# Soldeerbout_P3.net
KiCad netlist of a schematic drawn in Altium Designer
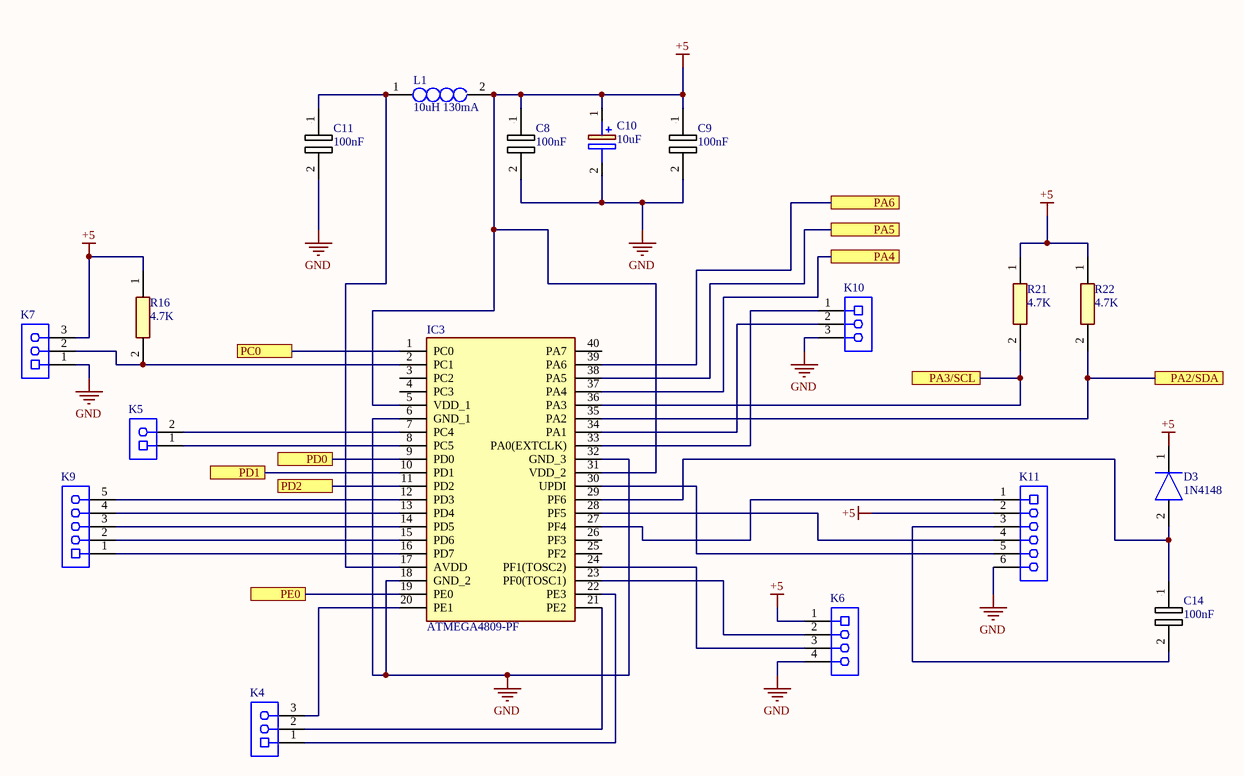
[diagram p0: Soldeerbout_P3.SchDoc]

(export (version "E")
  (design (tool "Eeschema 10.0.6"))
  (components
    (comp (ref "C8")
      (value "100nF")
      (footprint "SamacSys:0805")
      (description "Resistor")
      (fields (field (name "MANUFACTURER_PART_NUMBER") "ESR10EZPJ183"))
      (libsource (lib "SamacSys") (part "ESR10EZPJ183_1"))
    )
    (comp (ref "C9")
      (value "100nF")
      (footprint "SamacSys:0805")
      (description "Resistor")
      (fields (field (name "MANUFACTURER_PART_NUMBER") "ESR10EZPJ183"))
      (libsource (lib "SamacSys") (part "ESR10EZPJ183_1"))
    )
    (comp (ref "C10")
      (value "10uF")
      (footprint "SamacSys:C 50V 10µF")
      (description "Capacitor Polarised")
      (fields (field (name "MANUFACTURER_PART_NUMBER") "ESS106M050AE2AA"))
      (libsource (lib "SamacSys") (part "ESS106M050AE2AA"))
    )
    (comp (ref "C11")
      (value "100nF")
      (footprint "SamacSys:0805")
      (description "Resistor")
      (fields (field (name "MANUFACTURER_PART_NUMBER") "ESR10EZPJ183"))
      (libsource (lib "SamacSys") (part "ESR10EZPJ183_1"))
    )
    (comp (ref "C14")
      (value "100nF")
      (footprint "SamacSys:0805")
      (description "Resistor")
      (fields (field (name "MANUFACTURER_PART_NUMBER") "ESR10EZPJ183"))
      (libsource (lib "SamacSys") (part "ESR10EZPJ183_1"))
    )
    (comp (ref "D3")
      (value "1N4148")
      (footprint "SamacSys:1N4148, 100V 200mA")
      (description "Diode")
      (libsource (lib "SamacSys") (part "1N4148"))
    )
    (comp (ref "IC3")
      (value "ATMEGA4809-PF")
      (footprint "SamacSys:ic3")
      (description "Integrated Circuit")
      (fields (field (name "MOUSER2 PART NUMBER") "556-ATMEGA4809-PF"))
      (libsource (lib "SamacSys") (part "ATMEGA4809-PF"))
    )
    (comp (ref "K4")
      (value "61300311821")
      (footprint "61300311821")
      (description "WR-PHD Socket Header, THT, pitch 2.54mm, Single Row, Vertical, 3p")
      (fields (field (name "MANUFACTURER") "Wurth Elektronik"))
      (libsource (lib "") (part "61300311821_1"))
    )
    (comp (ref "K5")
      (value "61300211821")
      (footprint "61300211821")
      (description "WR-PHD Socket Header, THT, pitch 2.54mm, Single Row, Vertical, 2p")
      (fields (field (name "MANUFACTURER") "Wurth Elektronik"))
      (libsource (lib "SamacSys") (part "61300211821"))
    )
    (comp (ref "K6")
      (value "61300411821")
      (footprint "61300411821")
      (description "WR-PHD Socket Header, THT, pitch 2.54mm, Single Row, Vertical, 4p")
      (fields (field (name "MANUFACTURER") "Wurth Elektronik"))
      (libsource (lib "SamacSys") (part "61300411821"))
    )
    (comp (ref "K7")
      (value "61300311821")
      (footprint "61300311821")
      (description "WR-PHD Socket Header, THT, pitch 2.54mm, Single Row, Vertical, 3p")
      (fields (field (name "MANUFACTURER") "Wurth Elektronik"))
      (libsource (lib "") (part "61300311821_1"))
    )
    (comp (ref "K9")
      (value "61300511821")
      (footprint "61300511821")
      (description "WR-PHD Socket Header, THT, pitch 2.54mm, Single Row, Vertical, 5p")
      (fields (field (name "MANUFACTURER") "Wurth Elektronik"))
      (libsource (lib "SamacSys") (part "61300511821"))
    )
    (comp (ref "K10")
      (value "61300311821")
      (footprint "61300311821")
      (description "WR-PHD Socket Header, THT, pitch 2.54mm, Single Row, Vertical, 3p")
      (fields (field (name "MANUFACTURER") "Wurth Elektronik"))
      (libsource (lib "SamacSys") (part "61300311821"))
    )
    (comp (ref "K11")
      (value "61300611821")
      (footprint "61300611821")
      (description "WR-PHD Socket Header, THT, pitch 2.54mm, Single Row, Vertical, 6p")
      (fields (field (name "MANUFACTURER") "Wurth Elektronik"))
      (libsource (lib "SamacSys") (part "61300611821"))
    )
    (comp (ref "L1")
      (value "10uH 130mA")
      (footprint "SamacSys:L1 10uH 130mA")
      (description "Inductor")
      (fields
        (field (name "MOUSER2 PART NUMBER") "542-78F100-RC")
        (field (name "MANUFACTURER_PART_NUMBER") "78F100J-RC")
      )
      (libsource (lib "SamacSys") (part "78F100J-RC"))
    )
    (comp (ref "R16")
      (value "4.7K")
      (footprint "SamacSys:0805")
      (description "Resistor")
      (fields (field (name "MANUFACTURER_PART_NUMBER") "ESR10EZPJ183"))
      (libsource (lib "SamacSys") (part "ESR10EZPJ183"))
    )
    (comp (ref "R21")
      (value "4.7K")
      (footprint "SamacSys:0805")
      (description "Resistor")
      (fields (field (name "MANUFACTURER_PART_NUMBER") "ESR10EZPJ183"))
      (libsource (lib "SamacSys") (part "ESR10EZPJ183"))
    )
    (comp (ref "R22")
      (value "4.7K")
      (footprint "SamacSys:0805")
      (description "Resistor")
      (fields (field (name "MANUFACTURER_PART_NUMBER") "ESR10EZPJ183"))
      (libsource (lib "SamacSys") (part "ESR10EZPJ183"))
    )
  )
  (nets
    (net (code "1") (name "+5") (class "Default")
      (node (ref "C10") (pin "1") (pinfunction "+_1") (pintype "passive"))
      (node (ref "C8") (pin "1") (pinfunction "1_1") (pintype "passive"))
      (node (ref "C9") (pin "1") (pinfunction "1_1") (pintype "passive"))
      (node (ref "D3") (pin "1") (pinfunction "K_1") (pintype "passive"))
      (node (ref "IC3") (pin "31") (pinfunction "VDD_2_31") (pintype "passive"))
      (node (ref "IC3") (pin "5") (pinfunction "VDD_1_5") (pintype "passive"))
      (node (ref "K11") (pin "2") (pinfunction "2_2") (pintype "passive"))
      (node (ref "K6") (pin "1") (pinfunction "1_1") (pintype "passive"))
      (node (ref "K7") (pin "3") (pinfunction "3_3") (pintype "passive"))
      (node (ref "L1") (pin "2") (pinfunction "2_2") (pintype "passive"))
      (node (ref "R16") (pin "1") (pinfunction "1_1") (pintype "passive"))
      (node (ref "R21") (pin "1") (pinfunction "1_1") (pintype "passive"))
      (node (ref "R22") (pin "1") (pinfunction "1_1") (pintype "passive"))
    )
    (net (code "2") (name "/PA2{slash}SDA") (class "Default")
      (node (ref "IC3") (pin "35") (pinfunction "PA2_35") (pintype "passive"))
      (node (ref "R22") (pin "2") (pinfunction "2_2") (pintype "passive"))
    )
    (net (code "3") (name "/PA3{slash}SCL") (class "Default")
      (node (ref "IC3") (pin "36") (pinfunction "PA3_36") (pintype "passive"))
      (node (ref "R21") (pin "2") (pinfunction "2_2") (pintype "passive"))
    )
    (net (code "4") (name "/PA4") (class "Default")
      (node (ref "IC3") (pin "37") (pinfunction "PA4_37") (pintype "passive"))
    )
    (net (code "5") (name "/PA5") (class "Default")
      (node (ref "IC3") (pin "38") (pinfunction "PA5_38") (pintype "passive"))
    )
    (net (code "6") (name "/PA6") (class "Default")
      (node (ref "IC3") (pin "39") (pinfunction "PA6_39") (pintype "passive"))
    )
    (net (code "7") (name "/PC0") (class "Default")
      (node (ref "IC3") (pin "1") (pinfunction "PC0_1") (pintype "passive"))
    )
    (net (code "8") (name "/PD0") (class "Default")
      (node (ref "IC3") (pin "9") (pinfunction "PD0_9") (pintype "passive"))
    )
    (net (code "9") (name "/PD1") (class "Default")
      (node (ref "IC3") (pin "10") (pinfunction "PD1_10") (pintype "passive"))
    )
    (net (code "10") (name "/PD2") (class "Default")
      (node (ref "IC3") (pin "11") (pinfunction "PD2_11") (pintype "passive"))
    )
    (net (code "11") (name "/PE0") (class "Default")
      (node (ref "IC3") (pin "19") (pinfunction "PE0_19") (pintype "passive"))
    )
    (net (code "12") (name "GND") (class "Default")
      (node (ref "C10") (pin "2") (pinfunction "-_2") (pintype "passive"))
      (node (ref "C11") (pin "2") (pinfunction "2_2") (pintype "passive"))
      (node (ref "C8") (pin "2") (pinfunction "2_2") (pintype "passive"))
      (node (ref "C9") (pin "2") (pinfunction "2_2") (pintype "passive"))
      (node (ref "IC3") (pin "18") (pinfunction "GND_2_18") (pintype "passive"))
      (node (ref "IC3") (pin "32") (pinfunction "GND_3_32") (pintype "passive"))
      (node (ref "IC3") (pin "6") (pinfunction "GND_1_6") (pintype "passive"))
      (node (ref "K10") (pin "3") (pinfunction "3_3") (pintype "passive"))
      (node (ref "K11") (pin "6") (pinfunction "6_6") (pintype "passive"))
      (node (ref "K6") (pin "4") (pinfunction "4_4") (pintype "passive"))
      (node (ref "K7") (pin "1") (pinfunction "1_1") (pintype "passive"))
    )
    (net (code "13") (name "Net-(C14-Pad2)") (class "Default")
      (node (ref "C14") (pin "2") (pinfunction "2_2") (pintype "passive"))
      (node (ref "K11") (pin "3") (pinfunction "3_3") (pintype "passive"))
    )
    (net (code "14") (name "Net-(D3-A)") (class "Default")
      (node (ref "C14") (pin "1") (pinfunction "1_1") (pintype "passive"))
      (node (ref "D3") (pin "2") (pinfunction "A_2") (pintype "passive"))
      (node (ref "IC3") (pin "29") (pinfunction "PF6_29") (pintype "passive"))
    )
    (net (code "15") (name "Net-(IC3-AVDD)") (class "Default")
      (node (ref "C11") (pin "1") (pinfunction "1_1") (pintype "passive"))
      (node (ref "IC3") (pin "17") (pinfunction "AVDD_17") (pintype "passive"))
      (node (ref "L1") (pin "1") (pinfunction "1_1") (pintype "passive"))
    )
    (net (code "16") (name "Net-(IC3-PA0(EXTCLK))") (class "Default")
      (node (ref "IC3") (pin "33") (pinfunction "PA0(EXTCLK)_33") (pintype "passive"))
      (node (ref "K10") (pin "1") (pinfunction "1_1") (pintype "passive"))
    )
    (net (code "17") (name "Net-(IC3-PA1)") (class "Default")
      (node (ref "IC3") (pin "34") (pinfunction "PA1_34") (pintype "passive"))
      (node (ref "K10") (pin "2") (pinfunction "2_2") (pintype "passive"))
    )
    (net (code "18") (name "Net-(IC3-PC1)") (class "Default")
      (node (ref "IC3") (pin "2") (pinfunction "PC1_2") (pintype "passive"))
      (node (ref "K7") (pin "2") (pinfunction "2_2") (pintype "passive"))
      (node (ref "R16") (pin "2") (pinfunction "2_2") (pintype "passive"))
    )
    (net (code "19") (name "Net-(IC3-PC4)") (class "Default")
      (node (ref "IC3") (pin "7") (pinfunction "PC4_7") (pintype "passive"))
      (node (ref "K5") (pin "2") (pinfunction "2_2") (pintype "passive"))
    )
    (net (code "20") (name "Net-(IC3-PC5)") (class "Default")
      (node (ref "IC3") (pin "8") (pinfunction "PC5_8") (pintype "passive"))
      (node (ref "K5") (pin "1") (pinfunction "1_1") (pintype "passive"))
    )
    (net (code "21") (name "Net-(IC3-PD3)") (class "Default")
      (node (ref "IC3") (pin "12") (pinfunction "PD3_12") (pintype "passive"))
      (node (ref "K9") (pin "5") (pinfunction "5_5") (pintype "passive"))
    )
    (net (code "22") (name "Net-(IC3-PD4)") (class "Default")
      (node (ref "IC3") (pin "13") (pinfunction "PD4_13") (pintype "passive"))
      (node (ref "K9") (pin "4") (pinfunction "4_4") (pintype "passive"))
    )
    (net (code "23") (name "Net-(IC3-PD5)") (class "Default")
      (node (ref "IC3") (pin "14") (pinfunction "PD5_14") (pintype "passive"))
      (node (ref "K9") (pin "3") (pinfunction "3_3") (pintype "passive"))
    )
    (net (code "24") (name "Net-(IC3-PD6)") (class "Default")
      (node (ref "IC3") (pin "15") (pinfunction "PD6_15") (pintype "passive"))
      (node (ref "K9") (pin "2") (pinfunction "2_2") (pintype "passive"))
    )
    (net (code "25") (name "Net-(IC3-PD7)") (class "Default")
      (node (ref "IC3") (pin "16") (pinfunction "PD7_16") (pintype "passive"))
      (node (ref "K9") (pin "1") (pinfunction "1_1") (pintype "passive"))
    )
    (net (code "26") (name "Net-(IC3-PE1)") (class "Default")
      (node (ref "IC3") (pin "20") (pinfunction "PE1_20") (pintype "passive"))
      (node (ref "K4") (pin "3") (pinfunction "3_3") (pintype "passive"))
    )
    (net (code "27") (name "Net-(IC3-PE2)") (class "Default")
      (node (ref "IC3") (pin "21") (pinfunction "PE2_21") (pintype "passive"))
      (node (ref "K4") (pin "2") (pinfunction "2_2") (pintype "passive"))
    )
    (net (code "28") (name "Net-(IC3-PE3)") (class "Default")
      (node (ref "IC3") (pin "22") (pinfunction "PE3_22") (pintype "passive"))
      (node (ref "K4") (pin "1") (pinfunction "1_1") (pintype "passive"))
    )
    (net (code "29") (name "Net-(IC3-PF0(TOSC1))") (class "Default")
      (node (ref "IC3") (pin "23") (pinfunction "PF0(TOSC1)_23") (pintype "passive"))
      (node (ref "K6") (pin "2") (pinfunction "2_2") (pintype "passive"))
    )
    (net (code "30") (name "Net-(IC3-PF1(TOSC2))") (class "Default")
      (node (ref "IC3") (pin "24") (pinfunction "PF1(TOSC2)_24") (pintype "passive"))
      (node (ref "K6") (pin "3") (pinfunction "3_3") (pintype "passive"))
    )
    (net (code "31") (name "Net-(IC3-PF4)") (class "Default")
      (node (ref "IC3") (pin "27") (pinfunction "PF4_27") (pintype "passive"))
      (node (ref "K11") (pin "1") (pinfunction "1_1") (pintype "passive"))
    )
    (net (code "32") (name "Net-(IC3-PF5)") (class "Default")
      (node (ref "IC3") (pin "28") (pinfunction "PF5_28") (pintype "passive"))
      (node (ref "K11") (pin "4") (pinfunction "4_4") (pintype "passive"))
    )
    (net (code "33") (name "Net-(IC3-UPDI)") (class "Default")
      (node (ref "IC3") (pin "30") (pinfunction "UPDI_30") (pintype "passive"))
      (node (ref "K11") (pin "5") (pinfunction "5_5") (pintype "passive"))
    )
    (net (code "34") (name "unconnected-(IC3-PA7-Pad40)") (class "Default")
      (node (ref "IC3") (pin "40") (pinfunction "PA7_40") (pintype "passive"))
    )
    (net (code "35") (name "unconnected-(IC3-PC2-Pad3)") (class "Default")
      (node (ref "IC3") (pin "3") (pinfunction "PC2_3") (pintype "passive"))
    )
    (net (code "36") (name "unconnected-(IC3-PC3-Pad4)") (class "Default")
      (node (ref "IC3") (pin "4") (pinfunction "PC3_4") (pintype "passive"))
    )
    (net (code "37") (name "unconnected-(IC3-PF2-Pad25)") (class "Default")
      (node (ref "IC3") (pin "25") (pinfunction "PF2_25") (pintype "passive"))
    )
    (net (code "38") (name "unconnected-(IC3-PF3-Pad26)") (class "Default")
      (node (ref "IC3") (pin "26") (pinfunction "PF3_26") (pintype "passive"))
    )
  )
)
